# BQ2000_v3.net
KiCad netlist of a schematic drawn in EAGLE
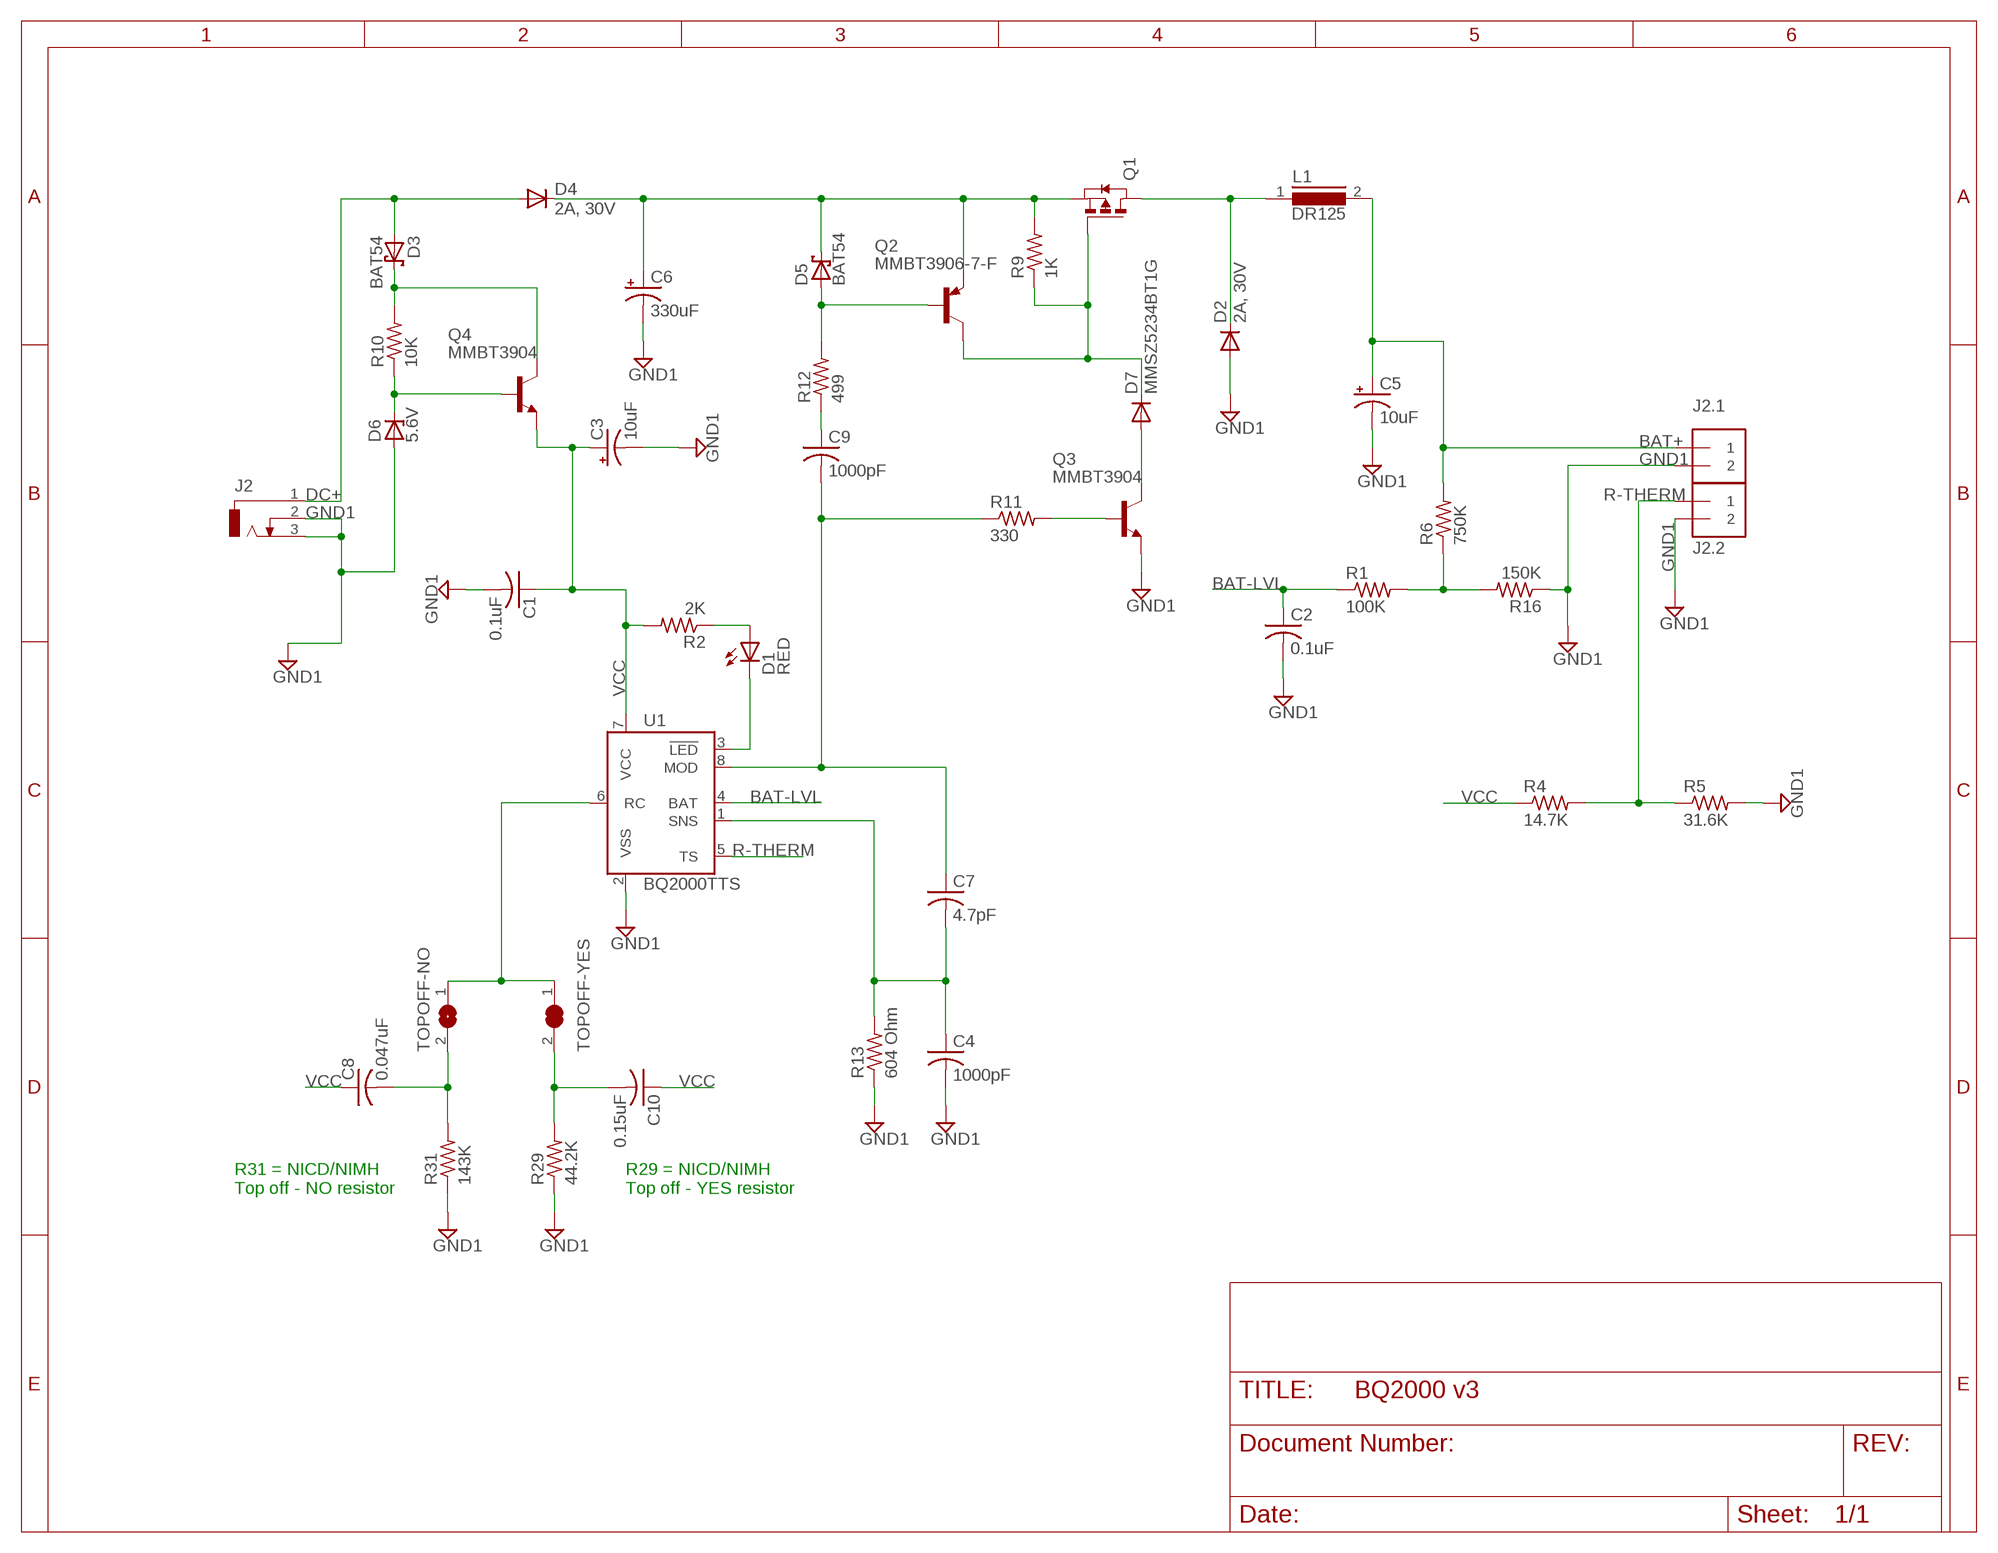
[diagram p0: schematic, sheet 1]

(export (version "E")
  (design (tool "Eeschema 10.0.6"))
  (components
    (comp (ref "C1")
      (value "0.1uF")
      (footprint "eagle-import:C0603K")
      (fields (field (name "MPN") "C0603C104K5RACTU"))
      (libsource (lib "eagle-import") (part "C-USC0603K"))
    )
    (comp (ref "C2")
      (value "0.1uF")
      (footprint "eagle-import:C0603K")
      (fields (field (name "MPN") "C0603C104K5RACTU"))
      (libsource (lib "eagle-import") (part "C-USC0603K"))
    )
    (comp (ref "C3")
      (value "10uF")
      (footprint "eagle-import:PANASONIC_C")
      (fields (field (name "MPN") "EEE-FK1E100R"))
      (libsource (lib "eagle-import") (part "CPOL-USC"))
    )
    (comp (ref "C4")
      (value "1000pF")
      (footprint "eagle-import:C0603K")
      (fields (field (name "MPN") "C0603C102K5RACTU"))
      (libsource (lib "eagle-import") (part "C-USC0603K"))
    )
    (comp (ref "C5")
      (value "10uF")
      (footprint "eagle-import:PANASONIC_C")
      (fields (field (name "MPN") "EEE-FK1E100R"))
      (libsource (lib "eagle-import") (part "CPOL-USC"))
    )
    (comp (ref "C6")
      (value "330uF")
      (footprint "eagle-import:PANASONIC_E")
      (fields (field (name "MPN") "EEE-FK1E331GP"))
      (libsource (lib "eagle-import") (part "CPOL-USE"))
    )
    (comp (ref "C7")
      (value "4.7pF")
      (footprint "eagle-import:C0603K")
      (fields (field (name "MPN") "C0603C479D5GACTU"))
      (libsource (lib "eagle-import") (part "C-USC0603K"))
    )
    (comp (ref "C8")
      (value "0.047uF")
      (footprint "eagle-import:C0603K")
      (fields (field (name "MPN") "C0603C473K3RACTU"))
      (libsource (lib "eagle-import") (part "C-USC0603K"))
    )
    (comp (ref "C9")
      (value "1000pF")
      (footprint "eagle-import:C0603K")
      (fields (field (name "MPN") "C0603C102K5RACTU"))
      (libsource (lib "eagle-import") (part "C-USC0603K"))
    )
    (comp (ref "C10")
      (value "0.15uF")
      (footprint "eagle-import:C0603K")
      (fields (field (name "MPN") "C0603C154K4RACTU"))
      (libsource (lib "eagle-import") (part "C-USC0603K"))
    )
    (comp (ref "D1")
      (value "RED")
      (footprint "eagle-import:CHIPLED_0805")
      (fields (field (name "MPN") "AP2012SRCPRV"))
      (libsource (lib "eagle-import") (part "LEDCHIPLED_0805"))
    )
    (comp (ref "D2")
      (value "2A, 30V")
      (footprint "eagle-import:SMB")
      (fields (field (name "MPN") "B230A-13-F"))
      (libsource (lib "eagle-import") (part "DIODE-SMB"))
    )
    (comp (ref "D3")
      (value "BAT54")
      (footprint "eagle-import:SOT23")
      (libsource (lib "eagle-import") (part "BAT54"))
    )
    (comp (ref "D4")
      (value "2A, 30V")
      (footprint "eagle-import:SMB")
      (fields (field (name "MPN") "B230A-13-F"))
      (libsource (lib "eagle-import") (part "DIODE-SMB"))
    )
    (comp (ref "D5")
      (value "BAT54")
      (footprint "eagle-import:SOT23")
      (libsource (lib "eagle-import") (part "BAT54"))
    )
    (comp (ref "D6")
      (value "5.6V")
      (footprint "eagle-import:SOT23")
      (fields (field (name "MPN") "BZX84C5V6"))
      (libsource (lib "eagle-import") (part "ZENER-DIODESOT23"))
    )
    (comp (ref "D7")
      (value "MMSZ5234BT1G")
      (footprint "eagle-import:SOD123")
      (libsource (lib "eagle-import") (part "DIODE-SOD123"))
    )
    (comp (ref "J2")
      (value "DCJ0303")
      (footprint "eagle-import:DCJ0303")
      (libsource (lib "eagle-import") (part "DCJ0303"))
    )
    (comp (ref "J2.1")
      (value "1X2-3.5MM")
      (footprint "eagle-import:1X2-3.5MM")
      (libsource (lib "eagle-import") (part "1X2-3.5MM"))
    )
    (comp (ref "J2.2")
      (value "1X2-3.5MM")
      (footprint "eagle-import:1X2-3.5MM")
      (libsource (lib "eagle-import") (part "1X2-3.5MM"))
    )
    (comp (ref "L1")
      (value "DR125")
      (footprint "eagle-import:DR125")
      (fields (field (name "MPN") "CDRH125NP-101MC"))
      (libsource (lib "eagle-import") (part "DR125"))
    )
    (comp (ref "Q1")
      (value "PMOSSOT23-6")
      (footprint "eagle-import:SOT23-6")
      (fields (field (name "MPN") "FDC658AP"))
      (libsource (lib "eagle-import") (part "PMOSSOT23-6"))
    )
    (comp (ref "Q2")
      (value "MMBT3906-7-F")
      (footprint "eagle-import:SOT23-BEC")
      (libsource (lib "eagle-import") (part "-PNP-SOT23-BECMMBT3906LT1"))
    )
    (comp (ref "Q3")
      (value "MMBT3904")
      (footprint "eagle-import:SOT23-BEC")
      (libsource (lib "eagle-import") (part "-NPN-SOT23-BECMMBT3904LT1"))
    )
    (comp (ref "Q4")
      (value "MMBT3904")
      (footprint "eagle-import:SOT23-BEC")
      (libsource (lib "eagle-import") (part "-NPN-SOT23-BECMMBT3904LT1"))
    )
    (comp (ref "R1")
      (value "100K")
      (footprint "eagle-import:R0603")
      (fields (field (name "MPN") "CRCW0603100KFKEA"))
      (libsource (lib "eagle-import") (part "R-US_R0603"))
    )
    (comp (ref "R2")
      (value "2K")
      (footprint "eagle-import:R0603")
      (fields (field (name "MPN") "CRCW06032K00FKEA"))
      (libsource (lib "eagle-import") (part "R-US_R0603"))
    )
    (comp (ref "R4")
      (value "14.7K")
      (footprint "eagle-import:R0603")
      (fields (field (name "MPN") "CRCW060314K7FKEA"))
      (libsource (lib "eagle-import") (part "R-US_R0603"))
    )
    (comp (ref "R5")
      (value "31.6K")
      (footprint "eagle-import:R0603")
      (fields (field (name "MPN") "CRCW060331K6FKEA"))
      (libsource (lib "eagle-import") (part "R-US_R0603"))
    )
    (comp (ref "R6")
      (value "750K")
      (footprint "eagle-import:R0603")
      (fields (field (name "MPN") "CRCW0603750KFKEA"))
      (libsource (lib "eagle-import") (part "R-US_R0603"))
    )
    (comp (ref "R9")
      (value "1K")
      (footprint "eagle-import:R0603")
      (fields (field (name "MPN") "CRCW06031K00FKEA"))
      (libsource (lib "eagle-import") (part "R-US_R0603"))
    )
    (comp (ref "R10")
      (value "10K")
      (footprint "eagle-import:R0603")
      (fields (field (name "MPN") "CRCW060310K0FKEA"))
      (libsource (lib "eagle-import") (part "R-US_R0603"))
    )
    (comp (ref "R11")
      (value "330")
      (footprint "eagle-import:R0603")
      (fields (field (name "MPN") "CRCW0603330RFKEA"))
      (libsource (lib "eagle-import") (part "R-US_R0603"))
    )
    (comp (ref "R12")
      (value "499")
      (footprint "eagle-import:R0603")
      (fields (field (name "MPN") "CRCW0603499RFKEA"))
      (libsource (lib "eagle-import") (part "R-US_R0603"))
    )
    (comp (ref "R13")
      (value "604 Ohm")
      (footprint "eagle-import:R0603")
      (fields (field (name "MPN") "CRCW0603604RFKEA"))
      (libsource (lib "eagle-import") (part "R-US_R0603"))
    )
    (comp (ref "R16")
      (value "150K")
      (footprint "eagle-import:R0603")
      (libsource (lib "eagle-import") (part "R-US_R0603"))
    )
    (comp (ref "R29")
      (value "44.2K")
      (footprint "eagle-import:R0603")
      (libsource (lib "eagle-import") (part "R-US_R0603"))
    )
    (comp (ref "R31")
      (value "143K")
      (footprint "eagle-import:R0603")
      (libsource (lib "eagle-import") (part "R-US_R0603"))
    )
    (comp (ref "TOPOFF-NO")
      (value "SOLDERJUMPER_OPEN")
      (footprint "eagle-import:SOLDERJUMPER_OPEN")
      (libsource (lib "eagle-import") (part "SOLDERJUMPER_OPEN"))
    )
    (comp (ref "TOPOFF-YES")
      (value "SOLDERJUMPER_CLOSED\"")
      (footprint "eagle-import:SOLDERJUMPER_CLOSED")
      (libsource (lib "eagle-import") (part "SOLDERJUMPER_CLOSED{dblquote}"))
    )
    (comp (ref "U1")
      (value "BQ2000TTS")
      (footprint "eagle-import:TSSOP8")
      (fields (field (name "MPN") "595-BQ2000PWR"))
      (libsource (lib "eagle-import") (part "BQ2000TTS"))
    )
  )
  (nets
    (net (code "1") (name "/BAT+") (class "Default")
      (node (ref "C5") (pin "+") (pinfunction "+_+") (pintype "passive"))
      (node (ref "J2.1") (pin "1") (pinfunction "1_1") (pintype "passive"))
      (node (ref "L1") (pin "2") (pinfunction "2_2") (pintype "passive"))
      (node (ref "R6") (pin "2") (pinfunction "2_2") (pintype "passive"))
    )
    (net (code "2") (name "/BAT-LVL") (class "Default")
      (node (ref "C2") (pin "1") (pinfunction "1_1") (pintype "passive"))
      (node (ref "R1") (pin "1") (pinfunction "1_1") (pintype "passive"))
      (node (ref "U1") (pin "4") (pinfunction "BAT_4") (pintype "input"))
    )
    (net (code "3") (name "/DC+") (class "Default")
      (node (ref "D3") (pin "1") (pinfunction "A_1") (pintype "passive"))
      (node (ref "D4") (pin "A") (pinfunction "A_A") (pintype "passive"))
      (node (ref "J2") (pin "1") (pinfunction "1_1") (pintype "passive"))
    )
    (net (code "4") (name "/R-THERM") (class "Default")
      (node (ref "J2.2") (pin "1") (pinfunction "1_1") (pintype "passive"))
      (node (ref "R4") (pin "2") (pinfunction "2_2") (pintype "passive"))
      (node (ref "R5") (pin "1") (pinfunction "1_1") (pintype "passive"))
      (node (ref "U1") (pin "5") (pinfunction "TS_5") (pintype "input"))
    )
    (net (code "5") (name "/VCC") (class "Default")
      (node (ref "C1") (pin "1") (pinfunction "1_1") (pintype "passive"))
      (node (ref "C10") (pin "1") (pinfunction "1_1") (pintype "passive"))
      (node (ref "C3") (pin "+") (pinfunction "+_+") (pintype "passive"))
      (node (ref "C8") (pin "1") (pinfunction "1_1") (pintype "passive"))
      (node (ref "Q4") (pin "E") (pinfunction "E_E") (pintype "passive"))
      (node (ref "R2") (pin "2") (pinfunction "2_2") (pintype "passive"))
      (node (ref "R4") (pin "1") (pinfunction "1_1") (pintype "passive"))
      (node (ref "U1") (pin "7") (pinfunction "VCC_7") (pintype "input"))
    )
    (net (code "6") (name "GND1") (class "Default")
      (node (ref "C1") (pin "2") (pinfunction "2_2") (pintype "passive"))
      (node (ref "C2") (pin "2") (pinfunction "2_2") (pintype "passive"))
      (node (ref "C3") (pin "-") (pinfunction "-_-") (pintype "passive"))
      (node (ref "C4") (pin "2") (pinfunction "2_2") (pintype "passive"))
      (node (ref "C5") (pin "-") (pinfunction "-_-") (pintype "passive"))
      (node (ref "C6") (pin "-") (pinfunction "-_-") (pintype "passive"))
      (node (ref "D2") (pin "A") (pinfunction "A_A") (pintype "passive"))
      (node (ref "D6") (pin "1") (pinfunction "A_1") (pintype "passive"))
      (node (ref "J2") (pin "2") (pinfunction "2_2") (pintype "passive"))
      (node (ref "J2") (pin "3") (pinfunction "3_3") (pintype "passive"))
      (node (ref "J2.1") (pin "2") (pinfunction "2_2") (pintype "passive"))
      (node (ref "J2.2") (pin "2") (pinfunction "2_2") (pintype "passive"))
      (node (ref "Q3") (pin "E") (pinfunction "E_E") (pintype "passive"))
      (node (ref "R13") (pin "1") (pinfunction "1_1") (pintype "passive"))
      (node (ref "R16") (pin "1") (pinfunction "1_1") (pintype "passive"))
      (node (ref "R29") (pin "1") (pinfunction "1_1") (pintype "passive"))
      (node (ref "R31") (pin "1") (pinfunction "1_1") (pintype "passive"))
      (node (ref "R5") (pin "2") (pinfunction "2_2") (pintype "passive"))
      (node (ref "U1") (pin "2") (pinfunction "VSS_2") (pintype "power_in"))
    )
    (net (code "7") (name "Net-(C8-Pad2)") (class "Default")
      (node (ref "C8") (pin "2") (pinfunction "2_2") (pintype "passive"))
      (node (ref "R31") (pin "2") (pinfunction "2_2") (pintype "passive"))
      (node (ref "TOPOFF-NO") (pin "2") (pinfunction "2_2") (pintype "passive"))
    )
    (net (code "8") (name "Net-(C9-Pad1)") (class "Default")
      (node (ref "C9") (pin "1") (pinfunction "1_1") (pintype "passive"))
      (node (ref "R12") (pin "1") (pinfunction "1_1") (pintype "passive"))
    )
    (net (code "9") (name "Net-(C10-Pad2)") (class "Default")
      (node (ref "C10") (pin "2") (pinfunction "2_2") (pintype "passive"))
      (node (ref "R29") (pin "2") (pinfunction "2_2") (pintype "passive"))
      (node (ref "TOPOFF-YES") (pin "2") (pinfunction "2_2") (pintype "passive"))
    )
    (net (code "10") (name "Net-(D1-PadA)") (class "Default")
      (node (ref "D1") (pin "A") (pinfunction "A_A") (pintype "passive"))
      (node (ref "R2") (pin "1") (pinfunction "1_1") (pintype "passive"))
    )
    (net (code "11") (name "Net-(D2-PadC)") (class "Default")
      (node (ref "D2") (pin "C") (pinfunction "C_C") (pintype "passive"))
      (node (ref "L1") (pin "1") (pinfunction "1_1") (pintype "passive"))
      (node (ref "Q1") (pin "1") (pinfunction "D_1") (pintype "passive"))
      (node (ref "Q1") (pin "2") (pinfunction "D_2") (pintype "passive"))
      (node (ref "Q1") (pin "5") (pinfunction "D_5") (pintype "passive"))
      (node (ref "Q1") (pin "6") (pinfunction "D_6") (pintype "passive"))
    )
    (net (code "12") (name "Net-(D3-C)") (class "Default")
      (node (ref "D3") (pin "3") (pinfunction "C_3") (pintype "passive"))
      (node (ref "Q4") (pin "C") (pinfunction "C_C") (pintype "passive"))
      (node (ref "R10") (pin "2") (pinfunction "2_2") (pintype "passive"))
    )
    (net (code "13") (name "Net-(D5-A)") (class "Default")
      (node (ref "D5") (pin "1") (pinfunction "A_1") (pintype "passive"))
      (node (ref "Q2") (pin "B") (pinfunction "B_B") (pintype "passive"))
      (node (ref "R12") (pin "2") (pinfunction "2_2") (pintype "passive"))
    )
    (net (code "14") (name "Net-(D5-C)") (class "Default")
      (node (ref "C6") (pin "+") (pinfunction "+_+") (pintype "passive"))
      (node (ref "D4") (pin "C") (pinfunction "C_C") (pintype "passive"))
      (node (ref "D5") (pin "3") (pinfunction "C_3") (pintype "passive"))
      (node (ref "Q1") (pin "4") (pinfunction "S_4") (pintype "passive"))
      (node (ref "Q2") (pin "E") (pinfunction "E_E") (pintype "passive"))
      (node (ref "R9") (pin "2") (pinfunction "2_2") (pintype "passive"))
    )
    (net (code "15") (name "Net-(D6-C)") (class "Default")
      (node (ref "D6") (pin "3") (pinfunction "C_3") (pintype "passive"))
      (node (ref "Q4") (pin "B") (pinfunction "B_B") (pintype "passive"))
      (node (ref "R10") (pin "1") (pinfunction "1_1") (pintype "passive"))
    )
    (net (code "16") (name "Net-(D7-PadA)") (class "Default")
      (node (ref "D7") (pin "A") (pinfunction "A_A") (pintype "passive"))
      (node (ref "Q3") (pin "C") (pinfunction "C_C") (pintype "passive"))
    )
    (net (code "17") (name "Net-(Q1-G)") (class "Default")
      (node (ref "D7") (pin "C") (pinfunction "C_C") (pintype "passive"))
      (node (ref "Q1") (pin "3") (pinfunction "G_3") (pintype "passive"))
      (node (ref "Q2") (pin "C") (pinfunction "C_C") (pintype "passive"))
      (node (ref "R9") (pin "1") (pinfunction "1_1") (pintype "passive"))
    )
    (net (code "18") (name "Net-(Q3-PadB)") (class "Default")
      (node (ref "Q3") (pin "B") (pinfunction "B_B") (pintype "passive"))
      (node (ref "R11") (pin "2") (pinfunction "2_2") (pintype "passive"))
    )
    (net (code "19") (name "Net-(R1-Pad2)") (class "Default")
      (node (ref "R1") (pin "2") (pinfunction "2_2") (pintype "passive"))
      (node (ref "R16") (pin "2") (pinfunction "2_2") (pintype "passive"))
      (node (ref "R6") (pin "1") (pinfunction "1_1") (pintype "passive"))
    )
    (net (code "20") (name "Net-(U1-MOD)") (class "Default")
      (node (ref "C7") (pin "1") (pinfunction "1_1") (pintype "passive"))
      (node (ref "C9") (pin "2") (pinfunction "2_2") (pintype "passive"))
      (node (ref "R11") (pin "1") (pinfunction "1_1") (pintype "passive"))
      (node (ref "U1") (pin "8") (pinfunction "MOD_8") (pintype "output"))
    )
    (net (code "21") (name "Net-(U1-RC)") (class "Default")
      (node (ref "TOPOFF-NO") (pin "1") (pinfunction "1_1") (pintype "passive"))
      (node (ref "TOPOFF-YES") (pin "1") (pinfunction "1_1") (pintype "passive"))
      (node (ref "U1") (pin "6") (pinfunction "RC_6") (pintype "input"))
    )
    (net (code "22") (name "Net-(U1-SNS)") (class "Default")
      (node (ref "C4") (pin "1") (pinfunction "1_1") (pintype "passive"))
      (node (ref "C7") (pin "2") (pinfunction "2_2") (pintype "passive"))
      (node (ref "R13") (pin "2") (pinfunction "2_2") (pintype "passive"))
      (node (ref "U1") (pin "1") (pinfunction "SNS_1") (pintype "input"))
    )
    (net (code "23") (name "Net-(U1-~{LED})") (class "Default")
      (node (ref "D1") (pin "C") (pinfunction "C_C") (pintype "passive"))
      (node (ref "U1") (pin "3") (pinfunction "~{LED}_3") (pintype "output"))
    )
  )
)
